# v001.net
KiCad netlist of a schematic drawn in EAGLE
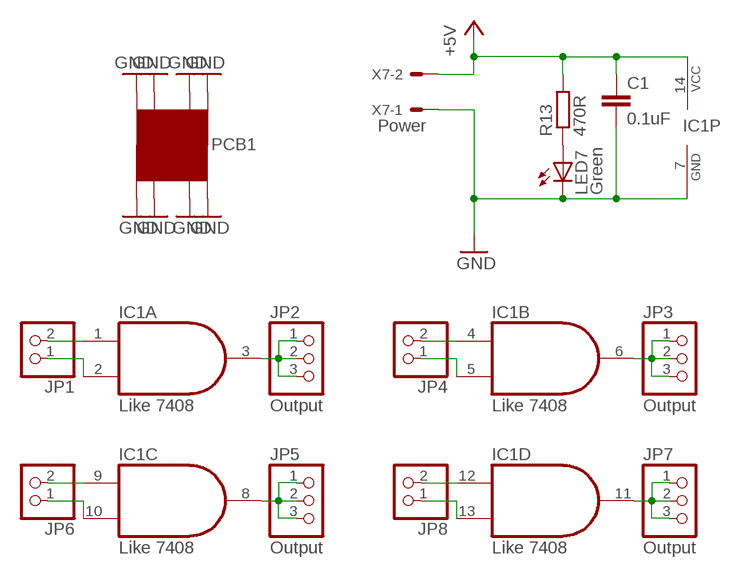
[diagram p0: schematic, sheet 1]

(export (version "E")
  (design (tool "Eeschema 10.0.6"))
  (components
    (comp (ref "C1")
      (value "0.1uF")
      (footprint "eagle-import:C050-024X044")
      (libsource (lib "eagle-import") (part "C-EU050-024X044"))
    )
    (comp (ref "IC1")
      (value "Like 7408")
      (footprint "eagle-import:DIL14")
      (libsource (lib "eagle-import") (part "7408NALS"))
    )
    (comp (ref "JP1")
      (value "PINHD-1X2")
      (footprint "eagle-import:1X02")
      (libsource (lib "eagle-import") (part "PINHD-1X2"))
    )
    (comp (ref "JP2")
      (value "Output")
      (footprint "eagle-import:1X03")
      (libsource (lib "eagle-import") (part "PINHD-1X3"))
    )
    (comp (ref "JP3")
      (value "Output")
      (footprint "eagle-import:1X03")
      (libsource (lib "eagle-import") (part "PINHD-1X3"))
    )
    (comp (ref "JP4")
      (value "PINHD-1X2")
      (footprint "eagle-import:1X02")
      (libsource (lib "eagle-import") (part "PINHD-1X2"))
    )
    (comp (ref "JP5")
      (value "Output")
      (footprint "eagle-import:1X03")
      (libsource (lib "eagle-import") (part "PINHD-1X3"))
    )
    (comp (ref "JP6")
      (value "PINHD-1X2")
      (footprint "eagle-import:1X02")
      (libsource (lib "eagle-import") (part "PINHD-1X2"))
    )
    (comp (ref "JP7")
      (value "Output")
      (footprint "eagle-import:1X03")
      (libsource (lib "eagle-import") (part "PINHD-1X3"))
    )
    (comp (ref "JP8")
      (value "PINHD-1X2")
      (footprint "eagle-import:1X02")
      (libsource (lib "eagle-import") (part "PINHD-1X2"))
    )
    (comp (ref "LED7")
      (value "Green")
      (footprint "eagle-import:LED3MM")
      (libsource (lib "eagle-import") (part "LED3MM"))
    )
    (comp (ref "PCB1")
      (value "PCB05X05")
      (footprint "eagle-import:PCB_05X05")
      (libsource (lib "eagle-import") (part "PCB05X05"))
    )
    (comp (ref "R13")
      (value "470R")
      (footprint "eagle-import:0204_7")
      (libsource (lib "eagle-import") (part "R-EU_0204/7"))
    )
    (comp (ref "X7")
      (value "Power")
      (footprint "eagle-import:6410-02")
      (libsource (lib "eagle-import") (part "22-?-0227-2021"))
    )
  )
  (nets
    (net (code "1") (name "+5V") (class "Default")
      (node (ref "C1") (pin "1") (pinfunction "1_1") (pintype "passive"))
      (node (ref "IC1") (pin "14") (pinfunction "VCC_14") (pintype "power_in"))
      (node (ref "R13") (pin "2") (pinfunction "2_2") (pintype "passive"))
      (node (ref "X7") (pin "2") (pinfunction "S_2") (pintype "passive"))
    )
    (net (code "2") (name "GND") (class "Default")
      (node (ref "C1") (pin "2") (pinfunction "2_2") (pintype "passive"))
      (node (ref "IC1") (pin "7") (pinfunction "GND_7") (pintype "power_in"))
      (node (ref "LED7") (pin "K") (pinfunction "C_K") (pintype "passive"))
      (node (ref "PCB1") (pin "GND@1") (pinfunction "GND_GND@1") (pintype "bidirectional"))
      (node (ref "PCB1") (pin "GND@2") (pinfunction "GND_GND@2") (pintype "bidirectional"))
      (node (ref "PCB1") (pin "GND@3") (pinfunction "GND_GND@3") (pintype "bidirectional"))
      (node (ref "PCB1") (pin "GND@4") (pinfunction "GND_GND@4") (pintype "bidirectional"))
      (node (ref "PCB1") (pin "GND@5") (pinfunction "GND_GND@5") (pintype "bidirectional"))
      (node (ref "PCB1") (pin "GND@6") (pinfunction "GND_GND@6") (pintype "bidirectional"))
      (node (ref "PCB1") (pin "GND@7") (pinfunction "GND_GND@7") (pintype "bidirectional"))
      (node (ref "PCB1") (pin "GND@8") (pinfunction "GND_GND@8") (pintype "bidirectional"))
      (node (ref "X7") (pin "1") (pinfunction "S_1") (pintype "passive"))
    )
    (net (code "3") (name "Net-(IC1A-I0)") (class "Default")
      (node (ref "IC1") (pin "1") (pinfunction "I0_1") (pintype "input"))
      (node (ref "JP1") (pin "2") (pinfunction "2_2") (pintype "passive"))
    )
    (net (code "4") (name "Net-(IC1A-I1)") (class "Default")
      (node (ref "IC1") (pin "2") (pinfunction "I1_2") (pintype "input"))
      (node (ref "JP1") (pin "1") (pinfunction "1_1") (pintype "passive"))
    )
    (net (code "5") (name "Net-(IC1A-O)") (class "Default")
      (node (ref "IC1") (pin "3") (pinfunction "O_3") (pintype "output"))
      (node (ref "JP2") (pin "1") (pinfunction "1_1") (pintype "passive"))
      (node (ref "JP2") (pin "2") (pinfunction "2_2") (pintype "passive"))
      (node (ref "JP2") (pin "3") (pinfunction "3_3") (pintype "passive"))
    )
    (net (code "6") (name "Net-(IC1B-I0)") (class "Default")
      (node (ref "IC1") (pin "4") (pinfunction "I0_4") (pintype "input"))
      (node (ref "JP4") (pin "2") (pinfunction "2_2") (pintype "passive"))
    )
    (net (code "7") (name "Net-(IC1B-I1)") (class "Default")
      (node (ref "IC1") (pin "5") (pinfunction "I1_5") (pintype "input"))
      (node (ref "JP4") (pin "1") (pinfunction "1_1") (pintype "passive"))
    )
    (net (code "8") (name "Net-(IC1B-O)") (class "Default")
      (node (ref "IC1") (pin "6") (pinfunction "O_6") (pintype "output"))
      (node (ref "JP3") (pin "1") (pinfunction "1_1") (pintype "passive"))
      (node (ref "JP3") (pin "2") (pinfunction "2_2") (pintype "passive"))
      (node (ref "JP3") (pin "3") (pinfunction "3_3") (pintype "passive"))
    )
    (net (code "9") (name "Net-(IC1C-I0)") (class "Default")
      (node (ref "IC1") (pin "9") (pinfunction "I0_9") (pintype "input"))
      (node (ref "JP6") (pin "2") (pinfunction "2_2") (pintype "passive"))
    )
    (net (code "10") (name "Net-(IC1C-I1)") (class "Default")
      (node (ref "IC1") (pin "10") (pinfunction "I1_10") (pintype "input"))
      (node (ref "JP6") (pin "1") (pinfunction "1_1") (pintype "passive"))
    )
    (net (code "11") (name "Net-(IC1C-O)") (class "Default")
      (node (ref "IC1") (pin "8") (pinfunction "O_8") (pintype "output"))
      (node (ref "JP5") (pin "1") (pinfunction "1_1") (pintype "passive"))
      (node (ref "JP5") (pin "2") (pinfunction "2_2") (pintype "passive"))
      (node (ref "JP5") (pin "3") (pinfunction "3_3") (pintype "passive"))
    )
    (net (code "12") (name "Net-(IC1D-I0)") (class "Default")
      (node (ref "IC1") (pin "12") (pinfunction "I0_12") (pintype "input"))
      (node (ref "JP8") (pin "2") (pinfunction "2_2") (pintype "passive"))
    )
    (net (code "13") (name "Net-(IC1D-I1)") (class "Default")
      (node (ref "IC1") (pin "13") (pinfunction "I1_13") (pintype "input"))
      (node (ref "JP8") (pin "1") (pinfunction "1_1") (pintype "passive"))
    )
    (net (code "14") (name "Net-(IC1D-O)") (class "Default")
      (node (ref "IC1") (pin "11") (pinfunction "O_11") (pintype "output"))
      (node (ref "JP7") (pin "1") (pinfunction "1_1") (pintype "passive"))
      (node (ref "JP7") (pin "2") (pinfunction "2_2") (pintype "passive"))
      (node (ref "JP7") (pin "3") (pinfunction "3_3") (pintype "passive"))
    )
    (net (code "15") (name "Net-(LED7-PadA)") (class "Default")
      (node (ref "LED7") (pin "A") (pinfunction "A_A") (pintype "passive"))
      (node (ref "R13") (pin "1") (pinfunction "1_1") (pintype "passive"))
    )
  )
)
